# COMS0006_TXDevMux.net
KiCad netlist of a schematic drawn in Altium Designer
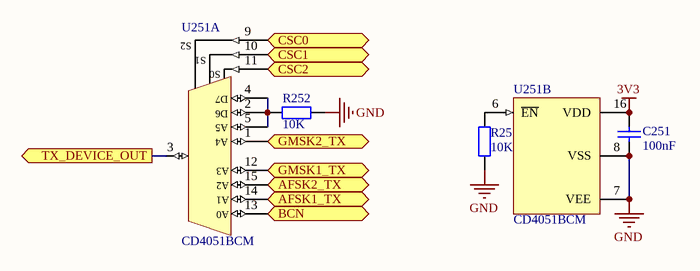
[diagram p0: COMS0006 TXDevMux.SchDoc]

(export (version "E")
  (design (tool "Eeschema 10.0.6"))
  (components
    (comp (ref "C251")
      (value "100nF")
      (footprint "CAP0603")
      (description "Capacitor")
      (fields (field (name "Comment") "Capacitor, ceramic"))
      (libsource (lib "Comms Board Small Footprints") (part "CAP0603"))
    )
    (comp (ref "R251")
      (value "10K")
      (footprint "RES0603")
      (description "Resistor")
      (fields (field (name "Comment") "Res1"))
      (libsource (lib "") (part "RES0603_1"))
    )
    (comp (ref "R252")
      (value "10K")
      (footprint "RES0603")
      (description "Resistor")
      (fields (field (name "Comment") "Res1"))
      (libsource (lib "Comms Board Small Footprints") (part "RES0603"))
    )
    (comp (ref "U251")
      (value "CD4051BCM")
      (footprint "Comms Board Small Footprints:TSSOP16")
      (description "8-Channel Analog Multiplexer/Demultiplexer")
      (libsource (lib "Comms Board Small Footprints") (part "CD4051BCM"))
    )
  )
  (nets
    (net (code "1") (name "/AFSK1_TX") (class "Default")
      (node (ref "U251") (pin "14") (pinfunction "A1_14") (pintype "bidirectional"))
    )
    (net (code "2") (name "/AFSK2_TX") (class "Default")
      (node (ref "U251") (pin "15") (pinfunction "A2_15") (pintype "bidirectional"))
    )
    (net (code "3") (name "/BCN") (class "Default")
      (node (ref "U251") (pin "13") (pinfunction "A0_13") (pintype "bidirectional"))
    )
    (net (code "4") (name "/CSC0") (class "Default")
      (node (ref "U251") (pin "9") (pinfunction "S2_9") (pintype "input"))
    )
    (net (code "5") (name "/CSC1") (class "Default")
      (node (ref "U251") (pin "10") (pinfunction "S1_10") (pintype "input"))
    )
    (net (code "6") (name "/CSC2") (class "Default")
      (node (ref "U251") (pin "11") (pinfunction "S0_11") (pintype "input"))
    )
    (net (code "7") (name "/GMSK1_TX") (class "Default")
      (node (ref "U251") (pin "12") (pinfunction "A3_12") (pintype "bidirectional"))
    )
    (net (code "8") (name "/GMSK2_TX") (class "Default")
      (node (ref "U251") (pin "1") (pinfunction "A4_1") (pintype "bidirectional"))
    )
    (net (code "9") (name "/TX_DEVICE_OUT") (class "Default")
      (node (ref "U251") (pin "3") (pinfunction "O_3") (pintype "bidirectional"))
    )
    (net (code "10") (name "3V3") (class "Default")
      (node (ref "C251") (pin "2") (pinfunction "2_2") (pintype "passive"))
      (node (ref "U251") (pin "16") (pinfunction "VDD_16") (pintype "power_in"))
    )
    (net (code "11") (name "GND") (class "Default")
      (node (ref "C251") (pin "1") (pinfunction "1_1") (pintype "passive"))
      (node (ref "R251") (pin "1") (pinfunction "1_1") (pintype "passive"))
      (node (ref "R252") (pin "1") (pinfunction "1_1") (pintype "passive"))
      (node (ref "U251") (pin "7") (pinfunction "VEE_7") (pintype "power_in"))
      (node (ref "U251") (pin "8") (pinfunction "VSS_8") (pintype "power_in"))
    )
    (net (code "12") (name "Net-(U251A-A5)") (class "Default")
      (node (ref "R252") (pin "2") (pinfunction "2_2") (pintype "passive"))
      (node (ref "U251") (pin "2") (pinfunction "A6_2") (pintype "bidirectional"))
      (node (ref "U251") (pin "4") (pinfunction "A7_4") (pintype "bidirectional"))
      (node (ref "U251") (pin "5") (pinfunction "A5_5") (pintype "bidirectional"))
    )
    (net (code "13") (name "Net-(U251B-~{EN})") (class "Default")
      (node (ref "R251") (pin "2") (pinfunction "2_2") (pintype "passive"))
      (node (ref "U251") (pin "6") (pinfunction "~{EN}_6") (pintype "input"))
    )
  )
)
